# AS3364_DG412_bus_mixer_v1_0.net
KiCad netlist of a schematic drawn in EAGLE
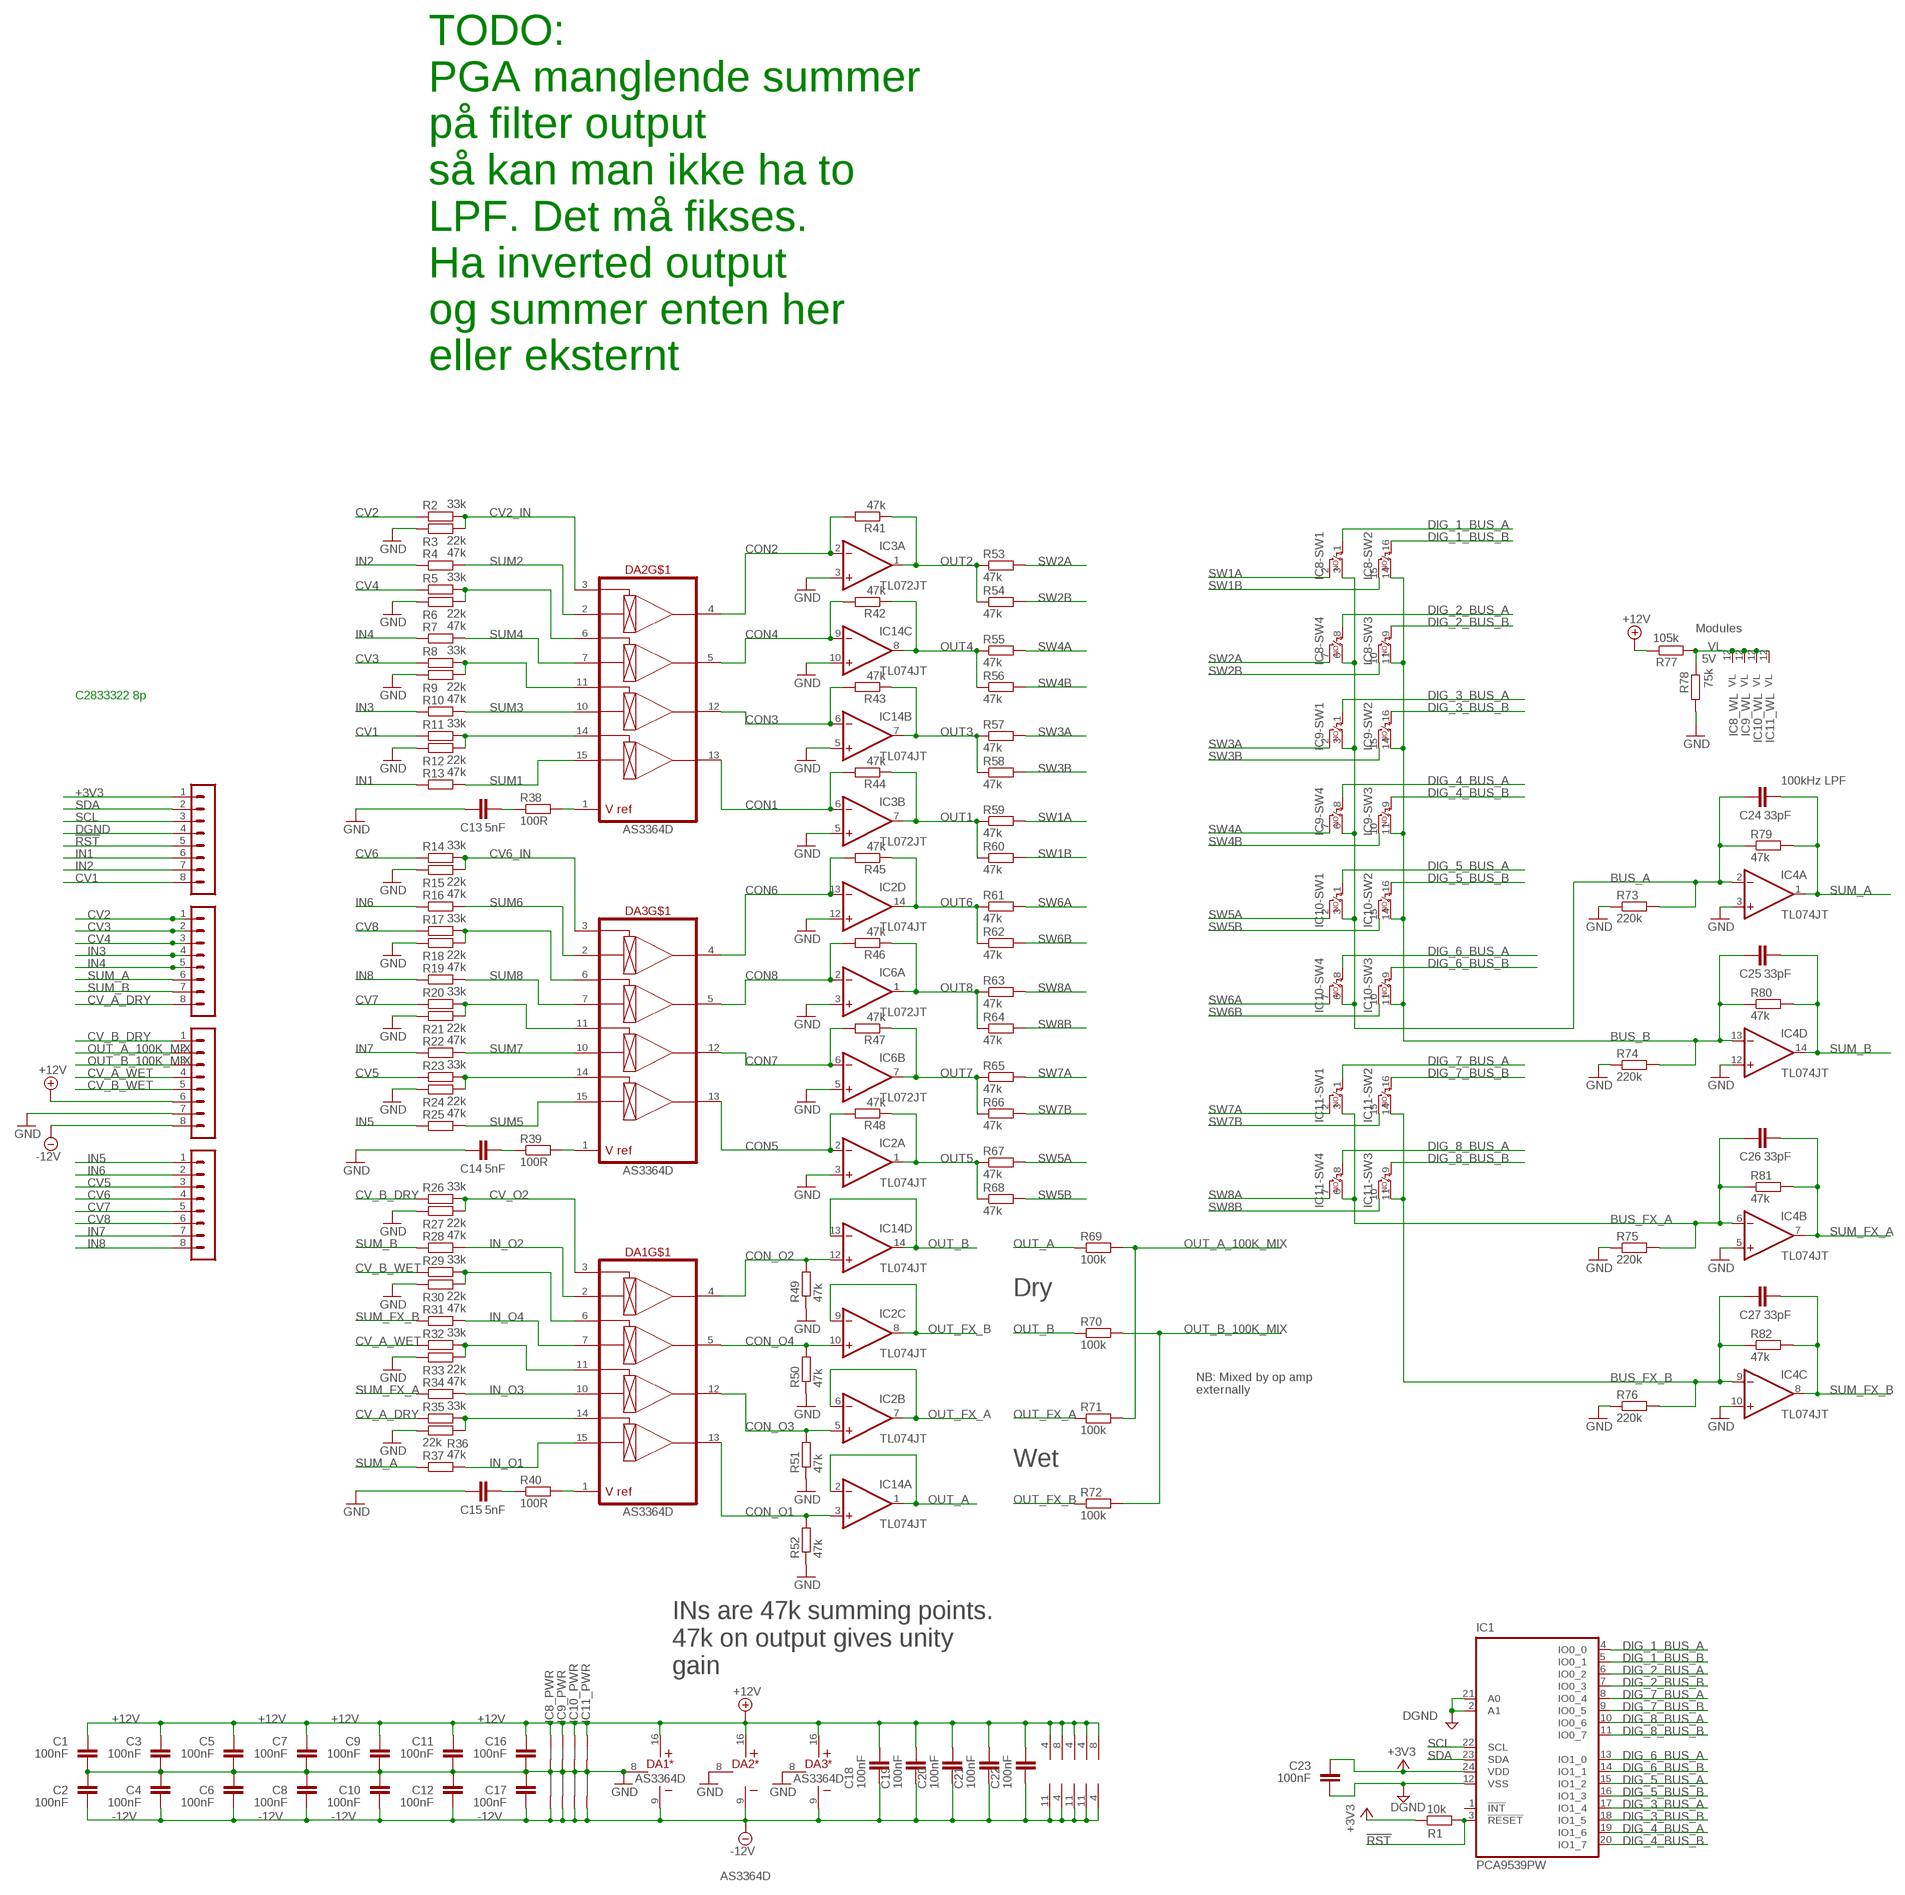
[diagram p0: schematic, sheet 1]

(export (version "E")
  (design (tool "Eeschema 10.0.6"))
  (components
    (comp (ref "C1")
      (value "100nF")
      (footprint "eagle-import:C0402")
      (libsource (lib "eagle-import") (part "C-EUC0402"))
    )
    (comp (ref "C2")
      (value "100nF")
      (footprint "eagle-import:C0402")
      (libsource (lib "eagle-import") (part "C-EUC0402"))
    )
    (comp (ref "C3")
      (value "100nF")
      (footprint "eagle-import:C0402")
      (libsource (lib "eagle-import") (part "C-EUC0402"))
    )
    (comp (ref "C4")
      (value "100nF")
      (footprint "eagle-import:C0402")
      (libsource (lib "eagle-import") (part "C-EUC0402"))
    )
    (comp (ref "C5")
      (value "100nF")
      (footprint "eagle-import:C0402")
      (libsource (lib "eagle-import") (part "C-EUC0402"))
    )
    (comp (ref "C6")
      (value "100nF")
      (footprint "eagle-import:C0402")
      (libsource (lib "eagle-import") (part "C-EUC0402"))
    )
    (comp (ref "C7")
      (value "100nF")
      (footprint "eagle-import:C0402")
      (libsource (lib "eagle-import") (part "C-EUC0402"))
    )
    (comp (ref "C8")
      (value "100nF")
      (footprint "eagle-import:C0402")
      (libsource (lib "eagle-import") (part "C-EUC0402"))
    )
    (comp (ref "C9")
      (value "100nF")
      (footprint "eagle-import:C0402")
      (libsource (lib "eagle-import") (part "C-EUC0402"))
    )
    (comp (ref "C10")
      (value "100nF")
      (footprint "eagle-import:C0402")
      (libsource (lib "eagle-import") (part "C-EUC0402"))
    )
    (comp (ref "C11")
      (value "100nF")
      (footprint "eagle-import:C0402")
      (libsource (lib "eagle-import") (part "C-EUC0402"))
    )
    (comp (ref "C12")
      (value "100nF")
      (footprint "eagle-import:C0402")
      (libsource (lib "eagle-import") (part "C-EUC0402"))
    )
    (comp (ref "C13")
      (value "5nF")
      (footprint "eagle-import:R0402")
      (libsource (lib "eagle-import") (part "C-EU-J"))
    )
    (comp (ref "C14")
      (value "5nF")
      (footprint "eagle-import:R0402")
      (libsource (lib "eagle-import") (part "C-EU-J"))
    )
    (comp (ref "C15")
      (value "5nF")
      (footprint "eagle-import:R0402")
      (libsource (lib "eagle-import") (part "C-EU-J"))
    )
    (comp (ref "C16")
      (value "100nF")
      (footprint "eagle-import:C0402")
      (libsource (lib "eagle-import") (part "C-EUC0402"))
    )
    (comp (ref "C17")
      (value "100nF")
      (footprint "eagle-import:C0402")
      (libsource (lib "eagle-import") (part "C-EUC0402"))
    )
    (comp (ref "C18")
      (value "100nF")
      (footprint "eagle-import:C0402")
      (libsource (lib "eagle-import") (part "C-EUC0402"))
    )
    (comp (ref "C19")
      (value "100nF")
      (footprint "eagle-import:C0402")
      (libsource (lib "eagle-import") (part "C-EUC0402"))
    )
    (comp (ref "C20")
      (value "100nF")
      (footprint "eagle-import:C0402")
      (libsource (lib "eagle-import") (part "C-EUC0402"))
    )
    (comp (ref "C21")
      (value "100nF")
      (footprint "eagle-import:C0402")
      (libsource (lib "eagle-import") (part "C-EUC0402"))
    )
    (comp (ref "C22")
      (value "100nF")
      (footprint "eagle-import:C0402")
      (libsource (lib "eagle-import") (part "C-EUC0402"))
    )
    (comp (ref "C23")
      (value "100nF")
      (footprint "eagle-import:C0402")
      (libsource (lib "eagle-import") (part "C-EUC0402"))
    )
    (comp (ref "C24")
      (value "33pF")
      (footprint "eagle-import:R0402")
      (libsource (lib "eagle-import") (part "C-EU-J"))
    )
    (comp (ref "C25")
      (value "33pF")
      (footprint "eagle-import:R0402")
      (libsource (lib "eagle-import") (part "C-EU-J"))
    )
    (comp (ref "C26")
      (value "33pF")
      (footprint "eagle-import:R0402")
      (libsource (lib "eagle-import") (part "C-EU-J"))
    )
    (comp (ref "C27")
      (value "33pF")
      (footprint "eagle-import:R0402")
      (libsource (lib "eagle-import") (part "C-EU-J"))
    )
    (comp (ref "DA1")
      (value "AS3364D")
      (footprint "eagle-import:DIL16J")
      (libsource (lib "eagle-import") (part "AS3364D"))
    )
    (comp (ref "DA2")
      (value "AS3364D")
      (footprint "eagle-import:DIL16J")
      (libsource (lib "eagle-import") (part "AS3364D"))
    )
    (comp (ref "DA3")
      (value "AS3364D")
      (footprint "eagle-import:DIL16J")
      (libsource (lib "eagle-import") (part "AS3364D"))
    )
    (comp (ref "IC1")
      (value "PCA9539PW")
      (footprint "eagle-import:TSSOP24J")
      (libsource (lib "eagle-import") (part "PCA9539PW"))
    )
    (comp (ref "IC2")
      (value "TL074JT")
      (footprint "eagle-import:TSSOP14J")
      (libsource (lib "eagle-import") (part "TL074JT"))
    )
    (comp (ref "IC3")
      (value "TL072JT")
      (footprint "eagle-import:TSSOP8J")
      (libsource (lib "eagle-import") (part "TL072JT"))
    )
    (comp (ref "IC4")
      (value "TL074JT")
      (footprint "eagle-import:TSSOP14J")
      (libsource (lib "eagle-import") (part "TL074JT"))
    )
    (comp (ref "IC6")
      (value "TL072JT")
      (footprint "eagle-import:TSSOP8J")
      (libsource (lib "eagle-import") (part "TL072JT"))
    )
    (comp (ref "IC8")
      (value "DG412-J")
      (footprint "eagle-import:DIL16J")
      (libsource (lib "eagle-import") (part "DG412-J"))
    )
    (comp (ref "IC9")
      (value "DG412-J")
      (footprint "eagle-import:DIL16J")
      (libsource (lib "eagle-import") (part "DG412-J"))
    )
    (comp (ref "IC10")
      (value "DG412-J")
      (footprint "eagle-import:DIL16J")
      (libsource (lib "eagle-import") (part "DG412-J"))
    )
    (comp (ref "IC11")
      (value "DG412-J")
      (footprint "eagle-import:DIL16J")
      (libsource (lib "eagle-import") (part "DG412-J"))
    )
    (comp (ref "IC14")
      (value "TL074JT")
      (footprint "eagle-import:TSSOP14J")
      (libsource (lib "eagle-import") (part "TL074JT"))
    )
    (comp (ref "R1")
      (value "10k")
      (footprint "eagle-import:R0402")
      (libsource (lib "eagle-import") (part "R-EU_R0402"))
    )
    (comp (ref "R2")
      (value "33k")
      (footprint "eagle-import:R0402")
      (libsource (lib "eagle-import") (part "R-EU_R0402"))
    )
    (comp (ref "R3")
      (value "22k")
      (footprint "eagle-import:R0402")
      (libsource (lib "eagle-import") (part "R-EU_R0402"))
    )
    (comp (ref "R4")
      (value "47k")
      (footprint "eagle-import:R0402")
      (libsource (lib "eagle-import") (part "R-EU_R0402"))
    )
    (comp (ref "R5")
      (value "33k")
      (footprint "eagle-import:R0402")
      (libsource (lib "eagle-import") (part "R-EU_R0402"))
    )
    (comp (ref "R6")
      (value "22k")
      (footprint "eagle-import:R0402")
      (libsource (lib "eagle-import") (part "R-EU_R0402"))
    )
    (comp (ref "R7")
      (value "47k")
      (footprint "eagle-import:R0402")
      (libsource (lib "eagle-import") (part "R-EU_R0402"))
    )
    (comp (ref "R8")
      (value "33k")
      (footprint "eagle-import:R0402")
      (libsource (lib "eagle-import") (part "R-EU_R0402"))
    )
    (comp (ref "R9")
      (value "22k")
      (footprint "eagle-import:R0402")
      (libsource (lib "eagle-import") (part "R-EU_R0402"))
    )
    (comp (ref "R10")
      (value "47k")
      (footprint "eagle-import:R0402")
      (libsource (lib "eagle-import") (part "R-EU_R0402"))
    )
    (comp (ref "R11")
      (value "33k")
      (footprint "eagle-import:R0402")
      (libsource (lib "eagle-import") (part "R-EU_R0402"))
    )
    (comp (ref "R12")
      (value "22k")
      (footprint "eagle-import:R0402")
      (libsource (lib "eagle-import") (part "R-EU_R0402"))
    )
    (comp (ref "R13")
      (value "47k")
      (footprint "eagle-import:R0402")
      (libsource (lib "eagle-import") (part "R-EU_R0402"))
    )
    (comp (ref "R14")
      (value "33k")
      (footprint "eagle-import:R0402")
      (libsource (lib "eagle-import") (part "R-EU_R0402"))
    )
    (comp (ref "R15")
      (value "22k")
      (footprint "eagle-import:R0402")
      (libsource (lib "eagle-import") (part "R-EU_R0402"))
    )
    (comp (ref "R16")
      (value "47k")
      (footprint "eagle-import:R0402")
      (libsource (lib "eagle-import") (part "R-EU_R0402"))
    )
    (comp (ref "R17")
      (value "33k")
      (footprint "eagle-import:R0402")
      (libsource (lib "eagle-import") (part "R-EU_R0402"))
    )
    (comp (ref "R18")
      (value "22k")
      (footprint "eagle-import:R0402")
      (libsource (lib "eagle-import") (part "R-EU_R0402"))
    )
    (comp (ref "R19")
      (value "47k")
      (footprint "eagle-import:R0402")
      (libsource (lib "eagle-import") (part "R-EU_R0402"))
    )
    (comp (ref "R20")
      (value "33k")
      (footprint "eagle-import:R0402")
      (libsource (lib "eagle-import") (part "R-EU_R0402"))
    )
    (comp (ref "R21")
      (value "22k")
      (footprint "eagle-import:R0402")
      (libsource (lib "eagle-import") (part "R-EU_R0402"))
    )
    (comp (ref "R22")
      (value "47k")
      (footprint "eagle-import:R0402")
      (libsource (lib "eagle-import") (part "R-EU_R0402"))
    )
    (comp (ref "R23")
      (value "33k")
      (footprint "eagle-import:R0402")
      (libsource (lib "eagle-import") (part "R-EU_R0402"))
    )
    (comp (ref "R24")
      (value "22k")
      (footprint "eagle-import:R0402")
      (libsource (lib "eagle-import") (part "R-EU_R0402"))
    )
    (comp (ref "R25")
      (value "47k")
      (footprint "eagle-import:R0402")
      (libsource (lib "eagle-import") (part "R-EU_R0402"))
    )
    (comp (ref "R26")
      (value "33k")
      (footprint "eagle-import:R0402")
      (libsource (lib "eagle-import") (part "R-EU_R0402"))
    )
    (comp (ref "R27")
      (value "22k")
      (footprint "eagle-import:R0402")
      (libsource (lib "eagle-import") (part "R-EU_R0402"))
    )
    (comp (ref "R28")
      (value "47k")
      (footprint "eagle-import:R0402")
      (libsource (lib "eagle-import") (part "R-EU_R0402"))
    )
    (comp (ref "R29")
      (value "33k")
      (footprint "eagle-import:R0402")
      (libsource (lib "eagle-import") (part "R-EU_R0402"))
    )
    (comp (ref "R30")
      (value "22k")
      (footprint "eagle-import:R0402")
      (libsource (lib "eagle-import") (part "R-EU_R0402"))
    )
    (comp (ref "R31")
      (value "47k")
      (footprint "eagle-import:R0402")
      (libsource (lib "eagle-import") (part "R-EU_R0402"))
    )
    (comp (ref "R32")
      (value "33k")
      (footprint "eagle-import:R0402")
      (libsource (lib "eagle-import") (part "R-EU_R0402"))
    )
    (comp (ref "R33")
      (value "22k")
      (footprint "eagle-import:R0402")
      (libsource (lib "eagle-import") (part "R-EU_R0402"))
    )
    (comp (ref "R34")
      (value "47k")
      (footprint "eagle-import:R0402")
      (libsource (lib "eagle-import") (part "R-EU_R0402"))
    )
    (comp (ref "R35")
      (value "33k")
      (footprint "eagle-import:R0402")
      (libsource (lib "eagle-import") (part "R-EU_R0402"))
    )
    (comp (ref "R36")
      (value "22k")
      (footprint "eagle-import:R0402")
      (libsource (lib "eagle-import") (part "R-EU_R0402"))
    )
    (comp (ref "R37")
      (value "47k")
      (footprint "eagle-import:R0402")
      (libsource (lib "eagle-import") (part "R-EU_R0402"))
    )
    (comp (ref "R38")
      (value "100R")
      (footprint "eagle-import:R0402")
      (libsource (lib "eagle-import") (part "R-EU_R0402"))
    )
    (comp (ref "R39")
      (value "100R")
      (footprint "eagle-import:R0402")
      (libsource (lib "eagle-import") (part "R-EU_R0402"))
    )
    (comp (ref "R40")
      (value "100R")
      (footprint "eagle-import:R0402")
      (libsource (lib "eagle-import") (part "R-EU_R0402"))
    )
    (comp (ref "R41")
      (value "47k")
      (footprint "eagle-import:R0402")
      (libsource (lib "eagle-import") (part "R-EU_R0402"))
    )
    (comp (ref "R42")
      (value "47k")
      (footprint "eagle-import:R0402")
      (libsource (lib "eagle-import") (part "R-EU_R0402"))
    )
    (comp (ref "R43")
      (value "47k")
      (footprint "eagle-import:R0402")
      (libsource (lib "eagle-import") (part "R-EU_R0402"))
    )
    (comp (ref "R44")
      (value "47k")
      (footprint "eagle-import:R0402")
      (libsource (lib "eagle-import") (part "R-EU_R0402"))
    )
    (comp (ref "R45")
      (value "47k")
      (footprint "eagle-import:R0402")
      (libsource (lib "eagle-import") (part "R-EU_R0402"))
    )
    (comp (ref "R46")
      (value "47k")
      (footprint "eagle-import:R0402")
      (libsource (lib "eagle-import") (part "R-EU_R0402"))
    )
    (comp (ref "R47")
      (value "47k")
      (footprint "eagle-import:R0402")
      (libsource (lib "eagle-import") (part "R-EU_R0402"))
    )
    (comp (ref "R48")
      (value "47k")
      (footprint "eagle-import:R0402")
      (libsource (lib "eagle-import") (part "R-EU_R0402"))
    )
    (comp (ref "R49")
      (value "47k")
      (footprint "eagle-import:R0402")
      (libsource (lib "eagle-import") (part "R-EU_R0402"))
    )
    (comp (ref "R50")
      (value "47k")
      (footprint "eagle-import:R0402")
      (libsource (lib "eagle-import") (part "R-EU_R0402"))
    )
    (comp (ref "R51")
      (value "47k")
      (footprint "eagle-import:R0402")
      (libsource (lib "eagle-import") (part "R-EU_R0402"))
    )
    (comp (ref "R52")
      (value "47k")
      (footprint "eagle-import:R0402")
      (libsource (lib "eagle-import") (part "R-EU_R0402"))
    )
    (comp (ref "R53")
      (value "47k")
      (footprint "eagle-import:R0402")
      (libsource (lib "eagle-import") (part "R-EU_R0402"))
    )
    (comp (ref "R54")
      (value "47k")
      (footprint "eagle-import:R0402")
      (libsource (lib "eagle-import") (part "R-EU_R0402"))
    )
    (comp (ref "R55")
      (value "47k")
      (footprint "eagle-import:R0402")
      (libsource (lib "eagle-import") (part "R-EU_R0402"))
    )
    (comp (ref "R56")
      (value "47k")
      (footprint "eagle-import:R0402")
      (libsource (lib "eagle-import") (part "R-EU_R0402"))
    )
    (comp (ref "R57")
      (value "47k")
      (footprint "eagle-import:R0402")
      (libsource (lib "eagle-import") (part "R-EU_R0402"))
    )
    (comp (ref "R58")
      (value "47k")
      (footprint "eagle-import:R0402")
      (libsource (lib "eagle-import") (part "R-EU_R0402"))
    )
    (comp (ref "R59")
      (value "47k")
      (footprint "eagle-import:R0402")
      (libsource (lib "eagle-import") (part "R-EU_R0402"))
    )
    (comp (ref "R60")
      (value "47k")
      (footprint "eagle-import:R0402")
      (libsource (lib "eagle-import") (part "R-EU_R0402"))
    )
    (comp (ref "R61")
      (value "47k")
      (footprint "eagle-import:R0402")
      (libsource (lib "eagle-import") (part "R-EU_R0402"))
    )
    (comp (ref "R62")
      (value "47k")
      (footprint "eagle-import:R0402")
      (libsource (lib "eagle-import") (part "R-EU_R0402"))
    )
    (comp (ref "R63")
      (value "47k")
      (footprint "eagle-import:R0402")
      (libsource (lib "eagle-import") (part "R-EU_R0402"))
    )
    (comp (ref "R64")
      (value "47k")
      (footprint "eagle-import:R0402")
      (libsource (lib "eagle-import") (part "R-EU_R0402"))
    )
    (comp (ref "R65")
      (value "47k")
      (footprint "eagle-import:R0402")
      (libsource (lib "eagle-import") (part "R-EU_R0402"))
    )
    (comp (ref "R66")
      (value "47k")
      (footprint "eagle-import:R0402")
      (libsource (lib "eagle-import") (part "R-EU_R0402"))
    )
    (comp (ref "R67")
      (value "47k")
      (footprint "eagle-import:R0402")
      (libsource (lib "eagle-import") (part "R-EU_R0402"))
    )
    (comp (ref "R68")
      (value "47k")
      (footprint "eagle-import:R0402")
      (libsource (lib "eagle-import") (part "R-EU_R0402"))
    )
    (comp (ref "R69")
      (value "100k")
      (footprint "eagle-import:R0402")
      (libsource (lib "eagle-import") (part "R-EU_R0402"))
    )
    (comp (ref "R70")
      (value "100k")
      (footprint "eagle-import:R0402")
      (libsource (lib "eagle-import") (part "R-EU_R0402"))
    )
    (comp (ref "R71")
      (value "100k")
      (footprint "eagle-import:R0402")
      (libsource (lib "eagle-import") (part "R-EU_R0402"))
    )
    (comp (ref "R72")
      (value "100k")
      (footprint "eagle-import:R0402")
      (libsource (lib "eagle-import") (part "R-EU_R0402"))
    )
    (comp (ref "R73")
      (value "220k")
      (footprint "eagle-import:R0402")
      (libsource (lib "eagle-import") (part "R-EU_R0402"))
    )
    (comp (ref "R74")
      (value "220k")
      (footprint "eagle-import:R0402")
      (libsource (lib "eagle-import") (part "R-EU_R0402"))
    )
    (comp (ref "R75")
      (value "220k")
      (footprint "eagle-import:R0402")
      (libsource (lib "eagle-import") (part "R-EU_R0402"))
    )
    (comp (ref "R76")
      (value "220k")
      (footprint "eagle-import:R0402")
      (libsource (lib "eagle-import") (part "R-EU_R0402"))
    )
    (comp (ref "R77")
      (value "105k")
      (footprint "eagle-import:R0402")
      (libsource (lib "eagle-import") (part "R-EU_R0402"))
    )
    (comp (ref "R78")
      (value "75k")
      (footprint "eagle-import:R0402")
      (libsource (lib "eagle-import") (part "R-EU_R0402"))
    )
    (comp (ref "R79")
      (value "47k")
      (footprint "eagle-import:R0402")
      (libsource (lib "eagle-import") (part "R-EU_R0402"))
    )
    (comp (ref "R80")
      (value "47k")
      (footprint "eagle-import:R0402")
      (libsource (lib "eagle-import") (part "R-EU_R0402"))
    )
    (comp (ref "R81")
      (value "47k")
      (footprint "eagle-import:R0402")
      (libsource (lib "eagle-import") (part "R-EU_R0402"))
    )
    (comp (ref "R82")
      (value "47k")
      (footprint "eagle-import:R0402")
      (libsource (lib "eagle-import") (part "R-EU_R0402"))
    )
    (comp (ref "SV1")
      (value "MA08-1JP")
      (footprint "eagle-import:SIP-PIN08-1J")
      (libsource (lib "eagle-import") (part "MA08-1JP"))
    )
    (comp (ref "SV3")
      (value "MA08-1JP")
      (footprint "eagle-import:SIP-PIN08-1J")
      (libsource (lib "eagle-import") (part "MA08-1JP"))
    )
    (comp (ref "SV4")
      (value "MA08-1JP")
      (footprint "eagle-import:SIP-PIN08-1J")
      (libsource (lib "eagle-import") (part "MA08-1JP"))
    )
    (comp (ref "SV33")
      (value "MA08-1JP")
      (footprint "eagle-import:SIP-PIN08-1J")
      (libsource (lib "eagle-import") (part "MA08-1JP"))
    )
  )
  (nets
    (net (code "1") (name "+3V3") (class "Default")
      (node (ref "C23") (pin "2") (pinfunction "2_2") (pintype "passive"))
      (node (ref "IC1") (pin "24") (pinfunction "VDD_24") (pintype "power_in"))
      (node (ref "R1") (pin "1") (pinfunction "1_1") (pintype "passive"))
      (node (ref "SV33") (pin "1") (pinfunction "1_1") (pintype "passive"))
    )
    (net (code "2") (name "+12V") (class "Default")
      (node (ref "C1") (pin "2") (pinfunction "2_2") (pintype "passive"))
      (node (ref "C11") (pin "2") (pinfunction "2_2") (pintype "passive"))
      (node (ref "C16") (pin "2") (pinfunction "2_2") (pintype "passive"))
      (node (ref "C18") (pin "2") (pinfunction "2_2") (pintype "passive"))
      (node (ref "C19") (pin "2") (pinfunction "2_2") (pintype "passive"))
      (node (ref "C20") (pin "2") (pinfunction "2_2") (pintype "passive"))
      (node (ref "C21") (pin "2") (pinfunction "2_2") (pintype "passive"))
      (node (ref "C22") (pin "2") (pinfunction "2_2") (pintype "passive"))
      (node (ref "C3") (pin "2") (pinfunction "2_2") (pintype "passive"))
      (node (ref "C5") (pin "2") (pinfunction "2_2") (pintype "passive"))
      (node (ref "C7") (pin "2") (pinfunction "2_2") (pintype "passive"))
      (node (ref "C9") (pin "2") (pinfunction "2_2") (pintype "passive"))
      (node (ref "DA1") (pin "16") (pinfunction "V+_16") (pintype "power_in"))
      (node (ref "DA2") (pin "16") (pinfunction "V+_16") (pintype "power_in"))
      (node (ref "DA3") (pin "16") (pinfunction "V+_16") (pintype "power_in"))
      (node (ref "IC10") (pin "13") (pinfunction "+15V_13") (pintype "power_in"))
      (node (ref "IC11") (pin "13") (pinfunction "+15V_13") (pintype "power_in"))
      (node (ref "IC14") (pin "4") (pinfunction "V+_4") (pintype "power_in"))
      (node (ref "IC2") (pin "4") (pinfunction "V+_4") (pintype "power_in"))
      (node (ref "IC3") (pin "8") (pinfunction "V+_8") (pintype "power_in"))
      (node (ref "IC4") (pin "4") (pinfunction "V+_4") (pintype "power_in"))
      (node (ref "IC6") (pin "8") (pinfunction "V+_8") (pintype "power_in"))
      (node (ref "IC8") (pin "13") (pinfunction "+15V_13") (pintype "power_in"))
      (node (ref "IC9") (pin "13") (pinfunction "+15V_13") (pintype "power_in"))
      (node (ref "R77") (pin "1") (pinfunction "1_1") (pintype "passive"))
      (node (ref "SV4") (pin "6") (pinfunction "6_6") (pintype "passive"))
    )
    (net (code "3") (name "-12V") (class "Default")
      (node (ref "C10") (pin "1") (pinfunction "1_1") (pintype "passive"))
      (node (ref "C12") (pin "1") (pinfunction "1_1") (pintype "passive"))
      (node (ref "C17") (pin "1") (pinfunction "1_1") (pintype "passive"))
      (node (ref "C18") (pin "1") (pinfunction "1_1") (pintype "passive"))
      (node (ref "C19") (pin "1") (pinfunction "1_1") (pintype "passive"))
      (node (ref "C2") (pin "1") (pinfunction "1_1") (pintype "passive"))
      (node (ref "C20") (pin "1") (pinfunction "1_1") (pintype "passive"))
      (node (ref "C21") (pin "1") (pinfunction "1_1") (pintype "passive"))
      (node (ref "C22") (pin "1") (pinfunction "1_1") (pintype "passive"))
      (node (ref "C4") (pin "1") (pinfunction "1_1") (pintype "passive"))
      (node (ref "C6") (pin "1") (pinfunction "1_1") (pintype "passive"))
      (node (ref "C8") (pin "1") (pinfunction "1_1") (pintype "passive"))
      (node (ref "DA1") (pin "9") (pinfunction "V-_9") (pintype "power_in"))
      (node (ref "DA2") (pin "9") (pinfunction "V-_9") (pintype "power_in"))
      (node (ref "DA3") (pin "9") (pinfunction "V-_9") (pintype "power_in"))
      (node (ref "IC10") (pin "4") (pinfunction "-15V_4") (pintype "power_in"))
      (node (ref "IC11") (pin "4") (pinfunction "-15V_4") (pintype "power_in"))
      (node (ref "IC14") (pin "11") (pinfunction "V-_11") (pintype "power_in"))
      (node (ref "IC2") (pin "11") (pinfunction "V-_11") (pintype "power_in"))
      (node (ref "IC3") (pin "4") (pinfunction "V-_4") (pintype "power_in"))
      (node (ref "IC4") (pin "11") (pinfunction "V-_11") (pintype "power_in"))
      (node (ref "IC6") (pin "4") (pinfunction "V-_4") (pintype "power_in"))
      (node (ref "IC8") (pin "4") (pinfunction "-15V_4") (pintype "power_in"))
      (node (ref "IC9") (pin "4") (pinfunction "-15V_4") (pintype "power_in"))
      (node (ref "SV4") (pin "8") (pinfunction "8_8") (pintype "passive"))
    )
    (net (code "4") (name "/BUS_A") (class "Default")
      (node (ref "C24") (pin "1") (pinfunction "1_1") (pintype "passive"))
      (node (ref "IC10") (pin "3") (pinfunction "S_3") (pintype "bidirectional"))
      (node (ref "IC10") (pin "6") (pinfunction "S_6") (pintype "bidirectional"))
      (node (ref "IC4") (pin "2") (pinfunction "-IN_2") (pintype "input"))
      (node (ref "IC8") (pin "3") (pinfunction "S_3") (pintype "bidirectional"))
      (node (ref "IC8") (pin "6") (pinfunction "S_6") (pintype "bidirectional"))
      (node (ref "IC9") (pin "3") (pinfunction "S_3") (pintype "bidirectional"))
      (node (ref "IC9") (pin "6") (pinfunction "S_6") (pintype "bidirectional"))
      (node (ref "R73") (pin "2") (pinfunction "2_2") (pintype "passive"))
      (node (ref "R79") (pin "1") (pinfunction "1_1") (pintype "passive"))
    )
    (net (code "5") (name "/BUS_B") (class "Default")
      (node (ref "C25") (pin "1") (pinfunction "1_1") (pintype "passive"))
      (node (ref "IC10") (pin "11") (pinfunction "S_11") (pintype "bidirectional"))
      (node (ref "IC10") (pin "14") (pinfunction "S_14") (pintype "bidirectional"))
      (node (ref "IC4") (pin "13") (pinfunction "-IN_13") (pintype "input"))
      (node (ref "IC8") (pin "11") (pinfunction "S_11") (pintype "bidirectional"))
      (node (ref "IC8") (pin "14") (pinfunction "S_14") (pintype "bidirectional"))
      (node (ref "IC9") (pin "11") (pinfunction "S_11") (pintype "bidirectional"))
      (node (ref "IC9") (pin "14") (pinfunction "S_14") (pintype "bidirectional"))
      (node (ref "R74") (pin "2") (pinfunction "2_2") (pintype "passive"))
      (node (ref "R80") (pin "1") (pinfunction "1_1") (pintype "passive"))
    )
    (net (code "6") (name "/BUS_FX_A") (class "Default")
      (node (ref "C26") (pin "1") (pinfunction "1_1") (pintype "passive"))
      (node (ref "IC11") (pin "3") (pinfunction "S_3") (pintype "bidirectional"))
      (node (ref "IC11") (pin "6") (pinfunction "S_6") (pintype "bidirectional"))
      (node (ref "IC4") (pin "6") (pinfunction "-IN_6") (pintype "input"))
      (node (ref "R75") (pin "2") (pinfunction "2_2") (pintype "passive"))
      (node (ref "R81") (pin "1") (pinfunction "1_1") (pintype "passive"))
    )
    (net (code "7") (name "/BUS_FX_B") (class "Default")
      (node (ref "C27") (pin "1") (pinfunction "1_1") (pintype "passive"))
      (node (ref "IC11") (pin "11") (pinfunction "S_11") (pintype "bidirectional"))
      (node (ref "IC11") (pin "14") (pinfunction "S_14") (pintype "bidirectional"))
      (node (ref "IC4") (pin "9") (pinfunction "-IN_9") (pintype "input"))
      (node (ref "R76") (pin "2") (pinfunction "2_2") (pintype "passive"))
      (node (ref "R82") (pin "1") (pinfunction "1_1") (pintype "passive"))
    )
    (net (code "8") (name "/CON1") (class "Default")
      (node (ref "DA2") (pin "13") (pinfunction "OUT4_13") (pintype "output"))
      (node (ref "IC3") (pin "6") (pinfunction "-IN_6") (pintype "input"))
      (node (ref "R44") (pin "2") (pinfunction "2_2") (pintype "passive"))
    )
    (net (code "9") (name "/CON2") (class "Default")
      (node (ref "DA2") (pin "4") (pinfunction "OUT1_4") (pintype "output"))
      (node (ref "IC3") (pin "2") (pinfunction "-IN_2") (pintype "input"))
      (node (ref "R41") (pin "2") (pinfunction "2_2") (pintype "passive"))
    )
    (net (code "10") (name "/CON3") (class "Default")
      (node (ref "DA2") (pin "12") (pinfunction "OUT3_12") (pintype "output"))
      (node (ref "IC14") (pin "6") (pinfunction "-IN_6") (pintype "input"))
      (node (ref "R43") (pin "2") (pinfunction "2_2") (pintype "passive"))
    )
    (net (code "11") (name "/CON4") (class "Default")
      (node (ref "DA2") (pin "5") (pinfunction "OUT2_5") (pintype "output"))
      (node (ref "IC14") (pin "9") (pinfunction "-IN_9") (pintype "input"))
      (node (ref "R42") (pin "2") (pinfunction "2_2") (pintype "passive"))
    )
    (net (code "12") (name "/CON5") (class "Default")
      (node (ref "DA3") (pin "13") (pinfunction "OUT4_13") (pintype "output"))
      (node (ref "IC2") (pin "2") (pinfunction "-IN_2") (pintype "input"))
      (node (ref "R48") (pin "2") (pinfunction "2_2") (pintype "passive"))
    )
    (net (code "13") (name "/CON6") (class "Default")
      (node (ref "DA3") (pin "4") (pinfunction "OUT1_4") (pintype "output"))
      (node (ref "IC2") (pin "13") (pinfunction "-IN_13") (pintype "input"))
      (node (ref "R45") (pin "2") (pinfunction "2_2") (pintype "passive"))
    )
    (net (code "14") (name "/CON7") (class "Default")
      (node (ref "DA3") (pin "12") (pinfunction "OUT3_12") (pintype "output"))
      (node (ref "IC6") (pin "6") (pinfunction "-IN_6") (pintype "input"))
      (node (ref "R47") (pin "2") (pinfunction "2_2") (pintype "passive"))
    )
    (net (code "15") (name "/CON8") (class "Default")
      (node (ref "DA3") (pin "5") (pinfunction "OUT2_5") (pintype "output"))
      (node (ref "IC6") (pin "2") (pinfunction "-IN_2") (pintype "input"))
      (node (ref "R46") (pin "2") (pinfunction "2_2") (pintype "passive"))
    )
    (net (code "16") (name "/CON_O1") (class "Default")
      (node (ref "DA1") (pin "13") (pinfunction "OUT4_13") (pintype "output"))
      (node (ref "IC14") (pin "3") (pinfunction "+IN_3") (pintype "input"))
      (node (ref "R52") (pin "2") (pinfunction "2_2") (pintype "passive"))
    )
    (net (code "17") (name "/CON_O2") (class "Default")
      (node (ref "DA1") (pin "4") (pinfunction "OUT1_4") (pintype "output"))
      (node (ref "IC14") (pin "12") (pinfunction "+IN_12") (pintype "input"))
      (node (ref "R49") (pin "2") (pinfunction "2_2") (pintype "passive"))
    )
    (net (code "18") (name "/CON_O3") (class "Default")
      (node (ref "DA1") (pin "12") (pinfunction "OUT3_12") (pintype "output"))
      (node (ref "IC2") (pin "5") (pinfunction "+IN_5") (pintype "input"))
      (node (ref "R51") (pin "2") (pinfunction "2_2") (pintype "passive"))
    )
    (net (code "19") (name "/CON_O4") (class "Default")
      (node (ref "DA1") (pin "5") (pinfunction "OUT2_5") (pintype "output"))
      (node (ref "IC2") (pin "10") (pinfunction "+IN_10") (pintype "input"))
      (node (ref "R50") (pin "2") (pinfunction "2_2") (pintype "passive"))
    )
    (net (code "20") (name "/CV1") (class "Default")
      (node (ref "R11") (pin "1") (pinfunction "1_1") (pintype "passive"))
      (node (ref "SV33") (pin "8") (pinfunction "8_8") (pintype "passive"))
    )
    (net (code "21") (name "/CV2") (class "Default")
      (node (ref "R2") (pin "1") (pinfunction "1_1") (pintype "passive"))
      (node (ref "SV1") (pin "1") (pinfunction "1_1") (pintype "passive"))
    )
    (net (code "22") (name "/CV2_IN") (class "Default")
      (node (ref "DA2") (pin "3") (pinfunction "CV1_3") (pintype "input"))
      (node (ref "R2") (pin "2") (pinfunction "2_2") (pintype "passive"))
      (node (ref "R3") (pin "2") (pinfunction "2_2") (pintype "passive"))
    )
    (net (code "23") (name "/CV3") (class "Default")
      (node (ref "R8") (pin "1") (pinfunction "1_1") (pintype "passive"))
      (node (ref "SV1") (pin "2") (pinfunction "2_2") (pintype "passive"))
    )
    (net (code "24") (name "/CV4") (class "Default")
      (node (ref "R5") (pin "1") (pinfunction "1_1") (pintype "passive"))
      (node (ref "SV1") (pin "3") (pinfunction "3_3") (pintype "passive"))
    )
    (net (code "25") (name "/CV5") (class "Default")
      (node (ref "R23") (pin "1") (pinfunction "1_1") (pintype "passive"))
      (node (ref "SV3") (pin "3") (pinfunction "3_3") (pintype "passive"))
    )
    (net (code "26") (name "/CV6") (class "Default")
      (node (ref "R14") (pin "1") (pinfunction "1_1") (pintype "passive"))
      (node (ref "SV3") (pin "4") (pinfunction "4_4") (pintype "passive"))
    )
    (net (code "27") (name "/CV6_IN") (class "Default")
      (node (ref "DA3") (pin "3") (pinfunction "CV1_3") (pintype "input"))
      (node (ref "R14") (pin "2") (pinfunction "2_2") (pintype "passive"))
      (node (ref "R15") (pin "2") (pinfunction "2_2") (pintype "passive"))
    )
    (net (code "28") (name "/CV7") (class "Default")
      (node (ref "R20") (pin "1") (pinfunction "1_1") (pintype "passive"))
      (node (ref "SV3") (pin "5") (pinfunction "5_5") (pintype "passive"))
    )
    (net (code "29") (name "/CV8") (class "Default")
      (node (ref "R17") (pin "1") (pinfunction "1_1") (pintype "passive"))
      (node (ref "SV3") (pin "6") (pinfunction "6_6") (pintype "passive"))
    )
    (net (code "30") (name "/CV_A_DRY") (class "Default")
      (node (ref "R35") (pin "1") (pinfunction "1_1") (pintype "passive"))
      (node (ref "SV1") (pin "8") (pinfunction "8_8") (pintype "passive"))
    )
    (net (code "31") (name "/CV_A_WET") (class "Default")
      (node (ref "R32") (pin "1") (pinfunction "1_1") (pintype "passive"))
      (node (ref "SV4") (pin "4") (pinfunction "4_4") (pintype "passive"))
    )
    (net (code "32") (name "/CV_B_DRY") (class "Default")
      (node (ref "R26") (pin "1") (pinfunction "1_1") (pintype "passive"))
      (node (ref "SV4") (pin "1") (pinfunction "1_1") (pintype "passive"))
    )
    (net (code "33") (name "/CV_B_WET") (class "Default")
      (node (ref "R29") (pin "1") (pinfunction "1_1") (pintype "passive"))
      (node (ref "SV4") (pin "5") (pinfunction "5_5") (pintype "passive"))
    )
    (net (code "34") (name "/CV_O2") (class "Default")
      (node (ref "DA1") (pin "3") (pinfunction "CV1_3") (pintype "input"))
      (node (ref "R26") (pin "2") (pinfunction "2_2") (pintype "passive"))
      (node (ref "R27") (pin "2") (pinfunction "2_2") (pintype "passive"))
    )
    (net (code "35") (name "/DIG_1_BUS_A") (class "Default")
      (node (ref "IC1") (pin "4") (pinfunction "IO0_0_4") (pintype "bidirectional"))
      (node (ref "IC8") (pin "1") (pinfunction "C_1") (pintype "bidirectional"))
    )
    (net (code "36") (name "/DIG_1_BUS_B") (class "Default")
      (node (ref "IC1") (pin "5") (pinfunction "IO0_1_5") (pintype "bidirectional"))
      (node (ref "IC8") (pin "16") (pinfunction "C_16") (pintype "bidirectional"))
    )
    (net (code "37") (name "/DIG_2_BUS_A") (class "Default")
      (node (ref "IC1") (pin "6") (pinfunction "IO0_2_6") (pintype "bidirectional"))
      (node (ref "IC8") (pin "8") (pinfunction "C_8") (pintype "bidirectional"))
    )
    (net (code "38") (name "/DIG_2_BUS_B") (class "Default")
      (node (ref "IC1") (pin "7") (pinfunction "IO0_3_7") (pintype "bidirectional"))
      (node (ref "IC8") (pin "9") (pinfunction "C_9") (pintype "bidirectional"))
    )
    (net (code "39") (name "/DIG_3_BUS_A") (class "Default")
      (node (ref "IC1") (pin "17") (pinfunction "IO1_4_17") (pintype "bidirectional"))
      (node (ref "IC9") (pin "1") (pinfunction "C_1") (pintype "bidirectional"))
    )
    (net (code "40") (name "/DIG_3_BUS_B") (class "Default")
      (node (ref "IC1") (pin "18") (pinfunction "IO1_5_18") (pintype "bidirectional"))
      (node (ref "IC9") (pin "16") (pinfunction "C_16") (pintype "bidirectional"))
    )
    (net (code "41") (name "/DIG_4_BUS_A") (class "Default")
      (node (ref "IC1") (pin "19") (pinfunction "IO1_6_19") (pintype "bidirectional"))
      (node (ref "IC9") (pin "8") (pinfunction "C_8") (pintype "bidirectional"))
    )
    (net (code "42") (name "/DIG_4_BUS_B") (class "Default")
      (node (ref "IC1") (pin "20") (pinfunction "IO1_7_20") (pintype "bidirectional"))
      (node (ref "IC9") (pin "9") (pinfunction "C_9") (pintype "bidirectional"))
    )
    (net (code "43") (name "/DIG_5_BUS_A") (class "Default")
      (node (ref "IC1") (pin "15") (pinfunction "IO1_2_15") (pintype "bidirectional"))
      (node (ref "IC10") (pin "1") (pinfunction "C_1") (pintype "bidirectional"))
    )
    (net (code "44") (name "/DIG_5_BUS_B") (class "Default")
      (node (ref "IC1") (pin "16") (pinfunction "IO1_3_16") (pintype "bidirectional"))
      (node (ref "IC10") (pin "16") (pinfunction "C_16") (pintype "bidirectional"))
    )
    (net (code "45") (name "/DIG_6_BUS_A") (class "Default")
      (node (ref "IC1") (pin "13") (pinfunction "IO1_0_13") (pintype "bidirectional"))
      (node (ref "IC10") (pin "8") (pinfunction "C_8") (pintype "bidirectional"))
    )
    (net (code "46") (name "/DIG_6_BUS_B") (class "Default")
      (node (ref "IC1") (pin "14") (pinfunction "IO1_1_14") (pintype "bidirectional"))
      (node (ref "IC10") (pin "9") (pinfunction "C_9") (pintype "bidirectional"))
    )
    (net (code "47") (name "/DIG_7_BUS_A") (class "Default")
      (node (ref "IC1") (pin "8") (pinfunction "IO0_4_8") (pintype "bidirectional"))
      (node (ref "IC11") (pin "1") (pinfunction "C_1") (pintype "bidirectional"))
    )
    (net (code "48") (name "/DIG_7_BUS_B") (class "Default")
      (node (ref "IC1") (pin "9") (pinfunction "IO0_5_9") (pintype "bidirectional"))
      (node (ref "IC11") (pin "16") (pinfunction "C_16") (pintype "bidirectional"))
    )
    (net (code "49") (name "/DIG_8_BUS_A") (class "Default")
      (node (ref "IC1") (pin "10") (pinfunction "IO0_6_10") (pintype "bidirectional"))
      (node (ref "IC11") (pin "8") (pinfunction "C_8") (pintype "bidirectional"))
    )
    (net (code "50") (name "/DIG_8_BUS_B") (class "Default")
      (node (ref "IC1") (pin "11") (pinfunction "IO0_7_11") (pintype "bidirectional"))
      (node (ref "IC11") (pin "9") (pinfunction "C_9") (pintype "bidirectional"))
    )
    (net (code "51") (name "/IN1") (class "Default")
      (node (ref "R13") (pin "1") (pinfunction "1_1") (pintype "passive"))
      (node (ref "SV33") (pin "6") (pinfunction "6_6") (pintype "passive"))
    )
    (net (code "52") (name "/IN2") (class "Default")
      (node (ref "R4") (pin "1") (pinfunction "1_1") (pintype "passive"))
      (node (ref "SV33") (pin "7") (pinfunction "7_7") (pintype "passive"))
    )
    (net (code "53") (name "/IN3") (class "Default")
      (node (ref "R10") (pin "1") (pinfunction "1_1") (pintype "passive"))
      (node (ref "SV1") (pin "4") (pinfunction "4_4") (pintype "passive"))
    )
    (net (code "54") (name "/IN4") (class "Default")
      (node (ref "R7") (pin "1") (pinfunction "1_1") (pintype "passive"))
      (node (ref "SV1") (pin "5") (pinfunction "5_5") (pintype "passive"))
    )
    (net (code "55") (name "/IN5") (class "Default")
      (node (ref "R25") (pin "1") (pinfunction "1_1") (pintype "passive"))
      (node (ref "SV3") (pin "1") (pinfunction "1_1") (pintype "passive"))
    )
    (net (code "56") (name "/IN6") (class "Default")
      (node (ref "R16") (pin "1") (pinfunction "1_1") (pintype "passive"))
      (node (ref "SV3") (pin "2") (pinfunction "2_2") (pintype "passive"))
    )
    (net (code "57") (name "/IN7") (class "Default")
      (node (ref "R22") (pin "1") (pinfunction "1_1") (pintype "passive"))
      (node (ref "SV3") (pin "7") (pinfunction "7_7") (pintype "passive"))
    )
    (net (code "58") (name "/IN8") (class "Default")
      (node (ref "R19") (pin "1") (pinfunction "1_1") (pintype "passive"))
      (node (ref "SV3") (pin "8") (pinfunction "8_8") (pintype "passive"))
    )
    (net (code "59") (name "/IN_O1") (class "Default")
      (node (ref "DA1") (pin "15") (pinfunction "IN4_15") (pintype "input"))
      (node (ref "R37") (pin "2") (pinfunction "2_2") (pintype "passive"))
    )
    (net (code "60") (name "/IN_O2") (class "Default")
      (node (ref "DA1") (pin "2") (pinfunction "IN1_2") (pintype "input"))
      (node (ref "R28") (pin "2") (pinfunction "2_2") (pintype "passive"))
    )
    (net (code "61") (name "/IN_O3") (class "Default")
      (node (ref "DA1") (pin "10") (pinfunction "IN3_10") (pintype "input"))
      (node (ref "R34") (pin "2") (pinfunction "2_2") (pintype "passive"))
    )
    (net (code "62") (name "/IN_O4") (class "Default")
      (node (ref "DA1") (pin "7") (pinfunction "IN2_7") (pintype "input"))
      (node (ref "R31") (pin "2") (pinfunction "2_2") (pintype "passive"))
    )
    (net (code "63") (name "/OUT1") (class "Default")
      (node (ref "IC3") (pin "7") (pinfunction "OUT_7") (pintype "output"))
      (node (ref "R44") (pin "1") (pinfunction "1_1") (pintype "passive"))
      (node (ref "R59") (pin "1") (pinfunction "1_1") (pintype "passive"))
      (node (ref "R60") (pin "1") (pinfunction "1_1") (pintype "passive"))
    )
    (net (code "64") (name "/OUT2") (class "Default")
      (node (ref "IC3") (pin "1") (pinfunction "OUT_1") (pintype "output"))
      (node (ref "R41") (pin "1") (pinfunction "1_1") (pintype "passive"))
      (node (ref "R53") (pin "1") (pinfunction "1_1") (pintype "passive"))
      (node (ref "R54") (pin "1") (pinfunction "1_1") (pintype "passive"))
    )
    (net (code "65") (name "/OUT3") (class "Default")
      (node (ref "IC14") (pin "7") (pinfunction "OUT_7") (pintype "output"))
      (node (ref "R43") (pin "1") (pinfunction "1_1") (pintype "passive"))
      (node (ref "R57") (pin "1") (pinfunction "1_1") (pintype "passive"))
      (node (ref "R58") (pin "1") (pinfunction "1_1") (pintype "passive"))
    )
    (net (code "66") (name "/OUT4") (class "Default")
      (node (ref "IC14") (pin "8") (pinfunction "OUT_8") (pintype "output"))
      (node (ref "R42") (pin "1") (pinfunction "1_1") (pintype "passive"))
      (node (ref "R55") (pin "1") (pinfunction "1_1") (pintype "passive"))
      (node (ref "R56") (pin "1") (pinfunction "1_1") (pintype "passive"))
    )
    (net (code "67") (name "/OUT5") (class "Default")
      (node (ref "IC2") (pin "1") (pinfunction "OUT_1") (pintype "output"))
      (node (ref "R48") (pin "1") (pinfunction "1_1") (pintype "passive"))
      (node (ref "R67") (pin "1") (pinfunction "1_1") (pintype "passive"))
      (node (ref "R68") (pin "1") (pinfunction "1_1") (pintype "passive"))
    )
    (net (code "68") (name "/OUT6") (class "Default")
      (node (ref "IC2") (pin "14") (pinfunction "OUT_14") (pintype "output"))
      (node (ref "R45") (pin "1") (pinfunction "1_1") (pintype "passive"))
      (node (ref "R61") (pin "1") (pinfunction "1_1") (pintype "passive"))
      (node (ref "R62") (pin "1") (pinfunction "1_1") (pintype "passive"))
    )
    (net (code "69") (name "/OUT7") (class "Default")
      (node (ref "IC6") (pin "7") (pinfunction "OUT_7") (pintype "output"))
      (node (ref "R47") (pin "1") (pinfunction "1_1") (pintype "passive"))
      (node (ref "R65") (pin "1") (pinfunction "1_1") (pintype "passive"))
      (node (ref "R66") (pin "1") (pinfunction "1_1") (pintype "passive"))
    )
    (net (code "70") (name "/OUT8") (class "Default")
      (node (ref "IC6") (pin "1") (pinfunction "OUT_1") (pintype "output"))
      (node (ref "R46") (pin "1") (pinfunction "1_1") (pintype "passive"))
      (node (ref "R63") (pin "1") (pinfunction "1_1") (pintype "passive"))
      (node (ref "R64") (pin "1") (pinfunction "1_1") (pintype "passive"))
    )
    (net (code "71") (name "/OUT_A") (class "Default")
      (node (ref "IC14") (pin "1") (pinfunction "OUT_1") (pintype "output"))
      (node (ref "IC14") (pin "2") (pinfunction "-IN_2") (pintype "input"))
      (node (ref "R69") (pin "1") (pinfunction "1_1") (pintype "passive"))
    )
    (net (code "72") (name "/OUT_A_100K_MIX") (class "Default")
      (node (ref "R69") (pin "2") (pinfunction "2_2") (pintype "passive"))
      (node (ref "R71") (pin "2") (pinfunction "2_2") (pintype "passive"))
      (node (ref "SV4") (pin "2") (pinfunction "2_2") (pintype "passive"))
    )
    (net (code "73") (name "/OUT_B") (class "Default")
      (node (ref "IC14") (pin "13") (pinfunction "-IN_13") (pintype "input"))
      (node (ref "IC14") (pin "14") (pinfunction "OUT_14") (pintype "output"))
      (node (ref "R70") (pin "1") (pinfunction "1_1") (pintype "passive"))
    )
    (net (code "74") (name "/OUT_B_100K_MIX") (class "Default")
      (node (ref "R70") (pin "2") (pinfunction "2_2") (pintype "passive"))
      (node (ref "R72") (pin "2") (pinfunction "2_2") (pintype "passive"))
      (node (ref "SV4") (pin "3") (pinfunction "3_3") (pintype "passive"))
    )
    (net (code "75") (name "/OUT_FX_A") (class "Default")
      (node (ref "IC2") (pin "6") (pinfunction "-IN_6") (pintype "input"))
      (node (ref "IC2") (pin "7") (pinfunction "OUT_7") (pintype "output"))
      (node (ref "R71") (pin "1") (pinfunction "1_1") (pintype "passive"))
    )
    (net (code "76") (name "/OUT_FX_B") (class "Default")
      (node (ref "IC2") (pin "8") (pinfunction "OUT_8") (pintype "output"))
      (node (ref "IC2") (pin "9") (pinfunction "-IN_9") (pintype "input"))
      (node (ref "R72") (pin "1") (pinfunction "1_1") (pintype "passive"))
    )
    (net (code "77") (name "/SCL") (class "Default")
      (node (ref "IC1") (pin "22") (pinfunction "SCL_22") (pintype "bidirectional"))
      (node (ref "SV33") (pin "3") (pinfunction "3_3") (pintype "passive"))
    )
    (net (code "78") (name "/SDA") (class "Default")
      (node (ref "IC1") (pin "23") (pinfunction "SDA_23") (pintype "bidirectional"))
      (node (ref "SV33") (pin "2") (pinfunction "2_2") (pintype "passive"))
    )
    (net (code "79") (name "/SUM1") (class "Default")
      (node (ref "DA2") (pin "15") (pinfunction "IN4_15") (pintype "input"))
      (node (ref "R13") (pin "2") (pinfunction "2_2") (pintype "passive"))
    )
    (net (code "80") (name "/SUM2") (class "Default")
      (node (ref "DA2") (pin "2") (pinfunction "IN1_2") (pintype "input"))
      (node (ref "R4") (pin "2") (pinfunction "2_2") (pintype "passive"))
    )
    (net (code "81") (name "/SUM3") (class "Default")
      (node (ref "DA2") (pin "10") (pinfunction "IN3_10") (pintype "input"))
      (node (ref "R10") (pin "2") (pinfunction "2_2") (pintype "passive"))
    )
    (net (code "82") (name "/SUM4") (class "Default")
      (node (ref "DA2") (pin "7") (pinfunction "IN2_7") (pintype "input"))
      (node (ref "R7") (pin "2") (pinfunction "2_2") (pintype "passive"))
    )
    (net (code "83") (name "/SUM5") (class "Default")
      (node (ref "DA3") (pin "15") (pinfunction "IN4_15") (pintype "input"))
      (node (ref "R25") (pin "2") (pinfunction "2_2") (pintype "passive"))
    )
    (net (code "84") (name "/SUM6") (class "Default")
      (node (ref "DA3") (pin "2") (pinfunction "IN1_2") (pintype "input"))
      (node (ref "R16") (pin "2") (pinfunction "2_2") (pintype "passive"))
    )
    (net (code "85") (name "/SUM7") (class "Default")
      (node (ref "DA3") (pin "10") (pinfunction "IN3_10") (pintype "input"))
      (node (ref "R22") (pin "2") (pinfunction "2_2") (pintype "passive"))
    )
    (net (code "86") (name "/SUM8") (class "Default")
      (node (ref "DA3") (pin "7") (pinfunction "IN2_7") (pintype "input"))
      (node (ref "R19") (pin "2") (pinfunction "2_2") (pintype "passive"))
    )
    (net (code "87") (name "/SUM_A") (class "Default")
      (node (ref "C24") (pin "2") (pinfunction "2_2") (pintype "passive"))
      (node (ref "IC4") (pin "1") (pinfunction "OUT_1") (pintype "output"))
      (node (ref "R37") (pin "1") (pinfunction "1_1") (pintype "passive"))
      (node (ref "R79") (pin "2") (pinfunction "2_2") (pintype "passive"))
      (node (ref "SV1") (pin "6") (pinfunction "6_6") (pintype "passive"))
    )
    (net (code "88") (name "/SUM_B") (class "Default")
      (node (ref "C25") (pin "2") (pinfunction "2_2") (pintype "passive"))
      (node (ref "IC4") (pin "14") (pinfunction "OUT_14") (pintype "output"))
      (node (ref "R28") (pin "1") (pinfunction "1_1") (pintype "passive"))
      (node (ref "R80") (pin "2") (pinfunction "2_2") (pintype "passive"))
      (node (ref "SV1") (pin "7") (pinfunction "7_7") (pintype "passive"))
    )
    (net (code "89") (name "/SUM_FX_A") (class "Default")
      (node (ref "C26") (pin "2") (pinfunction "2_2") (pintype "passive"))
      (node (ref "IC4") (pin "7") (pinfunction "OUT_7") (pintype "output"))
      (node (ref "R34") (pin "1") (pinfunction "1_1") (pintype "passive"))
      (node (ref "R81") (pin "2") (pinfunction "2_2") (pintype "passive"))
    )
    (net (code "90") (name "/SUM_FX_B") (class "Default")
      (node (ref "C27") (pin "2") (pinfunction "2_2") (pintype "passive"))
      (node (ref "IC4") (pin "8") (pinfunction "OUT_8") (pintype "output"))
      (node (ref "R31") (pin "1") (pinfunction "1_1") (pintype "passive"))
      (node (ref "R82") (pin "2") (pinfunction "2_2") (pintype "passive"))
    )
    (net (code "91") (name "/SW1A") (class "Default")
      (node (ref "IC8") (pin "2") (pinfunction "D_2") (pintype "bidirectional"))
      (node (ref "R59") (pin "2") (pinfunction "2_2") (pintype "passive"))
    )
    (net (code "92") (name "/SW1B") (class "Default")
      (node (ref "IC8") (pin "15") (pinfunction "D_15") (pintype "bidirectional"))
      (node (ref "R60") (pin "2") (pinfunction "2_2") (pintype "passive"))
    )
    (net (code "93") (name "/SW2A") (class "Default")
      (node (ref "IC8") (pin "7") (pinfunction "D_7") (pintype "bidirectional"))
      (node (ref "R53") (pin "2") (pinfunction "2_2") (pintype "passive"))
    )
    (net (code "94") (name "/SW2B") (class "Default")
      (node (ref "IC8") (pin "10") (pinfunction "D_10") (pintype "bidirectional"))
      (node (ref "R54") (pin "2") (pinfunction "2_2") (pintype "passive"))
    )
    (net (code "95") (name "/SW3A") (class "Default")
      (node (ref "IC9") (pin "2") (pinfunction "D_2") (pintype "bidirectional"))
      (node (ref "R57") (pin "2") (pinfunction "2_2") (pintype "passive"))
    )
    (net (code "96") (name "/SW3B") (class "Default")
      (node (ref "IC9") (pin "15") (pinfunction "D_15") (pintype "bidirectional"))
      (node (ref "R58") (pin "2") (pinfunction "2_2") (pintype "passive"))
    )
    (net (code "97") (name "/SW4A") (class "Default")
      (node (ref "IC9") (pin "7") (pinfunction "D_7") (pintype "bidirectional"))
      (node (ref "R55") (pin "2") (pinfunction "2_2") (pintype "passive"))
    )
    (net (code "98") (name "/SW4B") (class "Default")
      (node (ref "IC9") (pin "10") (pinfunction "D_10") (pintype "bidirectional"))
      (node (ref "R56") (pin "2") (pinfunction "2_2") (pintype "passive"))
    )
    (net (code "99") (name "/SW5A") (class "Default")
      (node (ref "IC10") (pin "2") (pinfunction "D_2") (pintype "bidirectional"))
      (node (ref "R67") (pin "2") (pinfunction "2_2") (pintype "passive"))
    )
    (net (code "100") (name "/SW5B") (class "Default")
      (node (ref "IC10") (pin "15") (pinfunction "D_15") (pintype "bidirectional"))
      (node (ref "R68") (pin "2") (pinfunction "2_2") (pintype "passive"))
    )
    (net (code "101") (name "/SW6A") (class "Default")
      (node (ref "IC10") (pin "7") (pinfunction "D_7") (pintype "bidirectional"))
      (node (ref "R61") (pin "2") (pinfunction "2_2") (pintype "passive"))
    )
    (net (code "102") (name "/SW6B") (class "Default")
      (node (ref "IC10") (pin "10") (pinfunction "D_10") (pintype "bidirectional"))
      (node (ref "R62") (pin "2") (pinfunction "2_2") (pintype "passive"))
    )
    (net (code "103") (name "/SW7A") (class "Default")
      (node (ref "IC11") (pin "2") (pinfunction "D_2") (pintype "bidirectional"))
      (node (ref "R65") (pin "2") (pinfunction "2_2") (pintype "passive"))
    )
    (net (code "104") (name "/SW7B") (class "Default")
      (node (ref "IC11") (pin "15") (pinfunction "D_15") (pintype "bidirectional"))
      (node (ref "R66") (pin "2") (pinfunction "2_2") (pintype "passive"))
    )
    (net (code "105") (name "/SW8A") (class "Default")
      (node (ref "IC11") (pin "7") (pinfunction "D_7") (pintype "bidirectional"))
      (node (ref "R63") (pin "2") (pinfunction "2_2") (pintype "passive"))
    )
    (net (code "106") (name "/SW8B") (class "Default")
      (node (ref "IC11") (pin "10") (pinfunction "D_10") (pintype "bidirectional"))
      (node (ref "R64") (pin "2") (pinfunction "2_2") (pintype "passive"))
    )
    (net (code "107") (name "/VL") (class "Default")
      (node (ref "IC10") (pin "12") (pinfunction "VL_12") (pintype "bidirectional"))
      (node (ref "IC11") (pin "12") (pinfunction "VL_12") (pintype "bidirectional"))
      (node (ref "IC8") (pin "12") (pinfunction "VL_12") (pintype "bidirectional"))
      (node (ref "IC9") (pin "12") (pinfunction "VL_12") (pintype "bidirectional"))
      (node (ref "R77") (pin "2") (pinfunction "2_2") (pintype "passive"))
      (node (ref "R78") (pin "1") (pinfunction "1_1") (pintype "passive"))
    )
    (net (code "108") (name "/~{RST}") (class "Default")
      (node (ref "IC1") (pin "3") (pinfunction "~{RESET}_3") (pintype "bidirectional"))
      (node (ref "R1") (pin "2") (pinfunction "2_2") (pintype "passive"))
      (node (ref "SV33") (pin "5") (pinfunction "5_5") (pintype "passive"))
    )
    (net (code "109") (name "DGND") (class "Default")
      (node (ref "C23") (pin "1") (pinfunction "1_1") (pintype "passive"))
      (node (ref "IC1") (pin "12") (pinfunction "VSS_12") (pintype "power_in"))
      (node (ref "IC1") (pin "2") (pinfunction "A1_2") (pintype "bidirectional"))
      (node (ref "IC1") (pin "21") (pinfunction "A0_21") (pintype "bidirectional"))
      (node (ref "SV33") (pin "4") (pinfunction "4_4") (pintype "passive"))
    )
    (net (code "110") (name "GND") (class "Default")
      (node (ref "C1") (pin "1") (pinfunction "1_1") (pintype "passive"))
      (node (ref "C10") (pin "2") (pinfunction "2_2") (pintype "passive"))
      (node (ref "C11") (pin "1") (pinfunction "1_1") (pintype "passive"))
      (node (ref "C12") (pin "2") (pinfunction "2_2") (pintype "passive"))
      (node (ref "C13") (pin "1") (pinfunction "1_1") (pintype "passive"))
      (node (ref "C14") (pin "1") (pinfunction "1_1") (pintype "passive"))
      (node (ref "C15") (pin "1") (pinfunction "1_1") (pintype "passive"))
      (node (ref "C16") (pin "1") (pinfunction "1_1") (pintype "passive"))
      (node (ref "C17") (pin "2") (pinfunction "2_2") (pintype "passive"))
      (node (ref "C2") (pin "2") (pinfunction "2_2") (pintype "passive"))
      (node (ref "C3") (pin "1") (pinfunction "1_1") (pintype "passive"))
      (node (ref "C4") (pin "2") (pinfunction "2_2") (pintype "passive"))
      (node (ref "C5") (pin "1") (pinfunction "1_1") (pintype "passive"))
      (node (ref "C6") (pin "2") (pinfunction "2_2") (pintype "passive"))
      (node (ref "C7") (pin "1") (pinfunction "1_1") (pintype "passive"))
      (node (ref "C8") (pin "2") (pinfunction "2_2") (pintype "passive"))
      (node (ref "C9") (pin "1") (pinfunction "1_1") (pintype "passive"))
      (node (ref "DA1") (pin "8") (pinfunction "GND_8") (pintype "power_in"))
      (node (ref "DA2") (pin "8") (pinfunction "GND_8") (pintype "power_in"))
      (node (ref "DA3") (pin "8") (pinfunction "GND_8") (pintype "power_in"))
      (node (ref "IC10") (pin "5") (pinfunction "AGND_5") (pintype "power_in"))
      (node (ref "IC11") (pin "5") (pinfunction "AGND_5") (pintype "power_in"))
      (node (ref "IC14") (pin "10") (pinfunction "+IN_10") (pintype "input"))
      (node (ref "IC14") (pin "5") (pinfunction "+IN_5") (pintype "input"))
      (node (ref "IC2") (pin "12") (pinfunction "+IN_12") (pintype "input"))
      (node (ref "IC2") (pin "3") (pinfunction "+IN_3") (pintype "input"))
      (node (ref "IC3") (pin "3") (pinfunction "+IN_3") (pintype "input"))
      (node (ref "IC3") (pin "5") (pinfunction "+IN_5") (pintype "input"))
      (node (ref "IC4") (pin "10") (pinfunction "+IN_10") (pintype "input"))
      (node (ref "IC4") (pin "12") (pinfunction "+IN_12") (pintype "input"))
      (node (ref "IC4") (pin "3") (pinfunction "+IN_3") (pintype "input"))
      (node (ref "IC4") (pin "5") (pinfunction "+IN_5") (pintype "input"))
      (node (ref "IC6") (pin "3") (pinfunction "+IN_3") (pintype "input"))
      (node (ref "IC6") (pin "5") (pinfunction "+IN_5") (pintype "input"))
      (node (ref "IC8") (pin "5") (pinfunction "AGND_5") (pintype "power_in"))
      (node (ref "IC9") (pin "5") (pinfunction "AGND_5") (pintype "power_in"))
      (node (ref "R12") (pin "1") (pinfunction "1_1") (pintype "passive"))
      (node (ref "R15") (pin "1") (pinfunction "1_1") (pintype "passive"))
      (node (ref "R18") (pin "1") (pinfunction "1_1") (pintype "passive"))
      (node (ref "R21") (pin "1") (pinfunction "1_1") (pintype "passive"))
      (node (ref "R24") (pin "1") (pinfunction "1_1") (pintype "passive"))
      (node (ref "R27") (pin "1") (pinfunction "1_1") (pintype "passive"))
      (node (ref "R3") (pin "1") (pinfunction "1_1") (pintype "passive"))
      (node (ref "R30") (pin "1") (pinfunction "1_1") (pintype "passive"))
      (node (ref "R33") (pin "1") (pinfunction "1_1") (pintype "passive"))
      (node (ref "R36") (pin "1") (pinfunction "1_1") (pintype "passive"))
      (node (ref "R49") (pin "1") (pinfunction "1_1") (pintype "passive"))
      (node (ref "R50") (pin "1") (pinfunction "1_1") (pintype "passive"))
      (node (ref "R51") (pin "1") (pinfunction "1_1") (pintype "passive"))
      (node (ref "R52") (pin "1") (pinfunction "1_1") (pintype "passive"))
      (node (ref "R6") (pin "1") (pinfunction "1_1") (pintype "passive"))
      (node (ref "R73") (pin "1") (pinfunction "1_1") (pintype "passive"))
      (node (ref "R74") (pin "1") (pinfunction "1_1") (pintype "passive"))
      (node (ref "R75") (pin "1") (pinfunction "1_1") (pintype "passive"))
      (node (ref "R76") (pin "1") (pinfunction "1_1") (pintype "passive"))
      (node (ref "R78") (pin "2") (pinfunction "2_2") (pintype "passive"))
      (node (ref "R9") (pin "1") (pinfunction "1_1") (pintype "passive"))
      (node (ref "SV4") (pin "7") (pinfunction "7_7") (pintype "passive"))
    )
    (net (code "111") (name "Net-(C13-Pad2)") (class "Default")
      (node (ref "C13") (pin "2") (pinfunction "2_2") (pintype "passive"))
      (node (ref "R38") (pin "1") (pinfunction "1_1") (pintype "passive"))
    )
    (net (code "112") (name "Net-(C14-Pad2)") (class "Default")
      (node (ref "C14") (pin "2") (pinfunction "2_2") (pintype "passive"))
      (node (ref "R39") (pin "1") (pinfunction "1_1") (pintype "passive"))
    )
    (net (code "113") (name "Net-(C15-Pad2)") (class "Default")
      (node (ref "C15") (pin "2") (pinfunction "2_2") (pintype "passive"))
      (node (ref "R40") (pin "1") (pinfunction "1_1") (pintype "passive"))
    )
    (net (code "114") (name "Net-(DA1B-CV2)") (class "Default")
      (node (ref "DA1") (pin "6") (pinfunction "CV2_6") (pintype "input"))
      (node (ref "R29") (pin "2") (pinfunction "2_2") (pintype "passive"))
      (node (ref "R30") (pin "2") (pinfunction "2_2") (pintype "passive"))
    )
    (net (code "115") (name "Net-(DA1B-CV3)") (class "Default")
      (node (ref "DA1") (pin "11") (pinfunction "CV3_11") (pintype "input"))
      (node (ref "R32") (pin "2") (pinfunction "2_2") (pintype "passive"))
      (node (ref "R33") (pin "2") (pinfunction "2_2") (pintype "passive"))
    )
    (net (code "116") (name "Net-(DA1B-CV4)") (class "Default")
      (node (ref "DA1") (pin "14") (pinfunction "CV4_14") (pintype "input"))
      (node (ref "R35") (pin "2") (pinfunction "2_2") (pintype "passive"))
      (node (ref "R36") (pin "2") (pinfunction "2_2") (pintype "passive"))
    )
    (net (code "117") (name "Net-(DA1B-VREF)") (class "Default")
      (node (ref "DA1") (pin "1") (pinfunction "VREF_1") (pintype "output"))
      (node (ref "R40") (pin "2") (pinfunction "2_2") (pintype "passive"))
    )
    (net (code "118") (name "Net-(DA2B-CV2)") (class "Default")
      (node (ref "DA2") (pin "6") (pinfunction "CV2_6") (pintype "input"))
      (node (ref "R5") (pin "2") (pinfunction "2_2") (pintype "passive"))
      (node (ref "R6") (pin "2") (pinfunction "2_2") (pintype "passive"))
    )
    (net (code "119") (name "Net-(DA2B-CV3)") (class "Default")
      (node (ref "DA2") (pin "11") (pinfunction "CV3_11") (pintype "input"))
      (node (ref "R8") (pin "2") (pinfunction "2_2") (pintype "passive"))
      (node (ref "R9") (pin "2") (pinfunction "2_2") (pintype "passive"))
    )
    (net (code "120") (name "Net-(DA2B-CV4)") (class "Default")
      (node (ref "DA2") (pin "14") (pinfunction "CV4_14") (pintype "input"))
      (node (ref "R11") (pin "2") (pinfunction "2_2") (pintype "passive"))
      (node (ref "R12") (pin "2") (pinfunction "2_2") (pintype "passive"))
    )
    (net (code "121") (name "Net-(DA2B-VREF)") (class "Default")
      (node (ref "DA2") (pin "1") (pinfunction "VREF_1") (pintype "output"))
      (node (ref "R38") (pin "2") (pinfunction "2_2") (pintype "passive"))
    )
    (net (code "122") (name "Net-(DA3B-CV2)") (class "Default")
      (node (ref "DA3") (pin "6") (pinfunction "CV2_6") (pintype "input"))
      (node (ref "R17") (pin "2") (pinfunction "2_2") (pintype "passive"))
      (node (ref "R18") (pin "2") (pinfunction "2_2") (pintype "passive"))
    )
    (net (code "123") (name "Net-(DA3B-CV3)") (class "Default")
      (node (ref "DA3") (pin "11") (pinfunction "CV3_11") (pintype "input"))
      (node (ref "R20") (pin "2") (pinfunction "2_2") (pintype "passive"))
      (node (ref "R21") (pin "2") (pinfunction "2_2") (pintype "passive"))
    )
    (net (code "124") (name "Net-(DA3B-CV4)") (class "Default")
      (node (ref "DA3") (pin "14") (pinfunction "CV4_14") (pintype "input"))
      (node (ref "R23") (pin "2") (pinfunction "2_2") (pintype "passive"))
      (node (ref "R24") (pin "2") (pinfunction "2_2") (pintype "passive"))
    )
    (net (code "125") (name "Net-(DA3B-VREF)") (class "Default")
      (node (ref "DA3") (pin "1") (pinfunction "VREF_1") (pintype "output"))
      (node (ref "R39") (pin "2") (pinfunction "2_2") (pintype "passive"))
    )
    (net (code "126") (name "unconnected-(IC1-~{INT}-Pad1)") (class "Default")
      (node (ref "IC1") (pin "1") (pinfunction "~{INT}_1") (pintype "bidirectional"))
    )
  )
)
